# led_projek.net
KiCad netlist of a schematic drawn in EAGLE
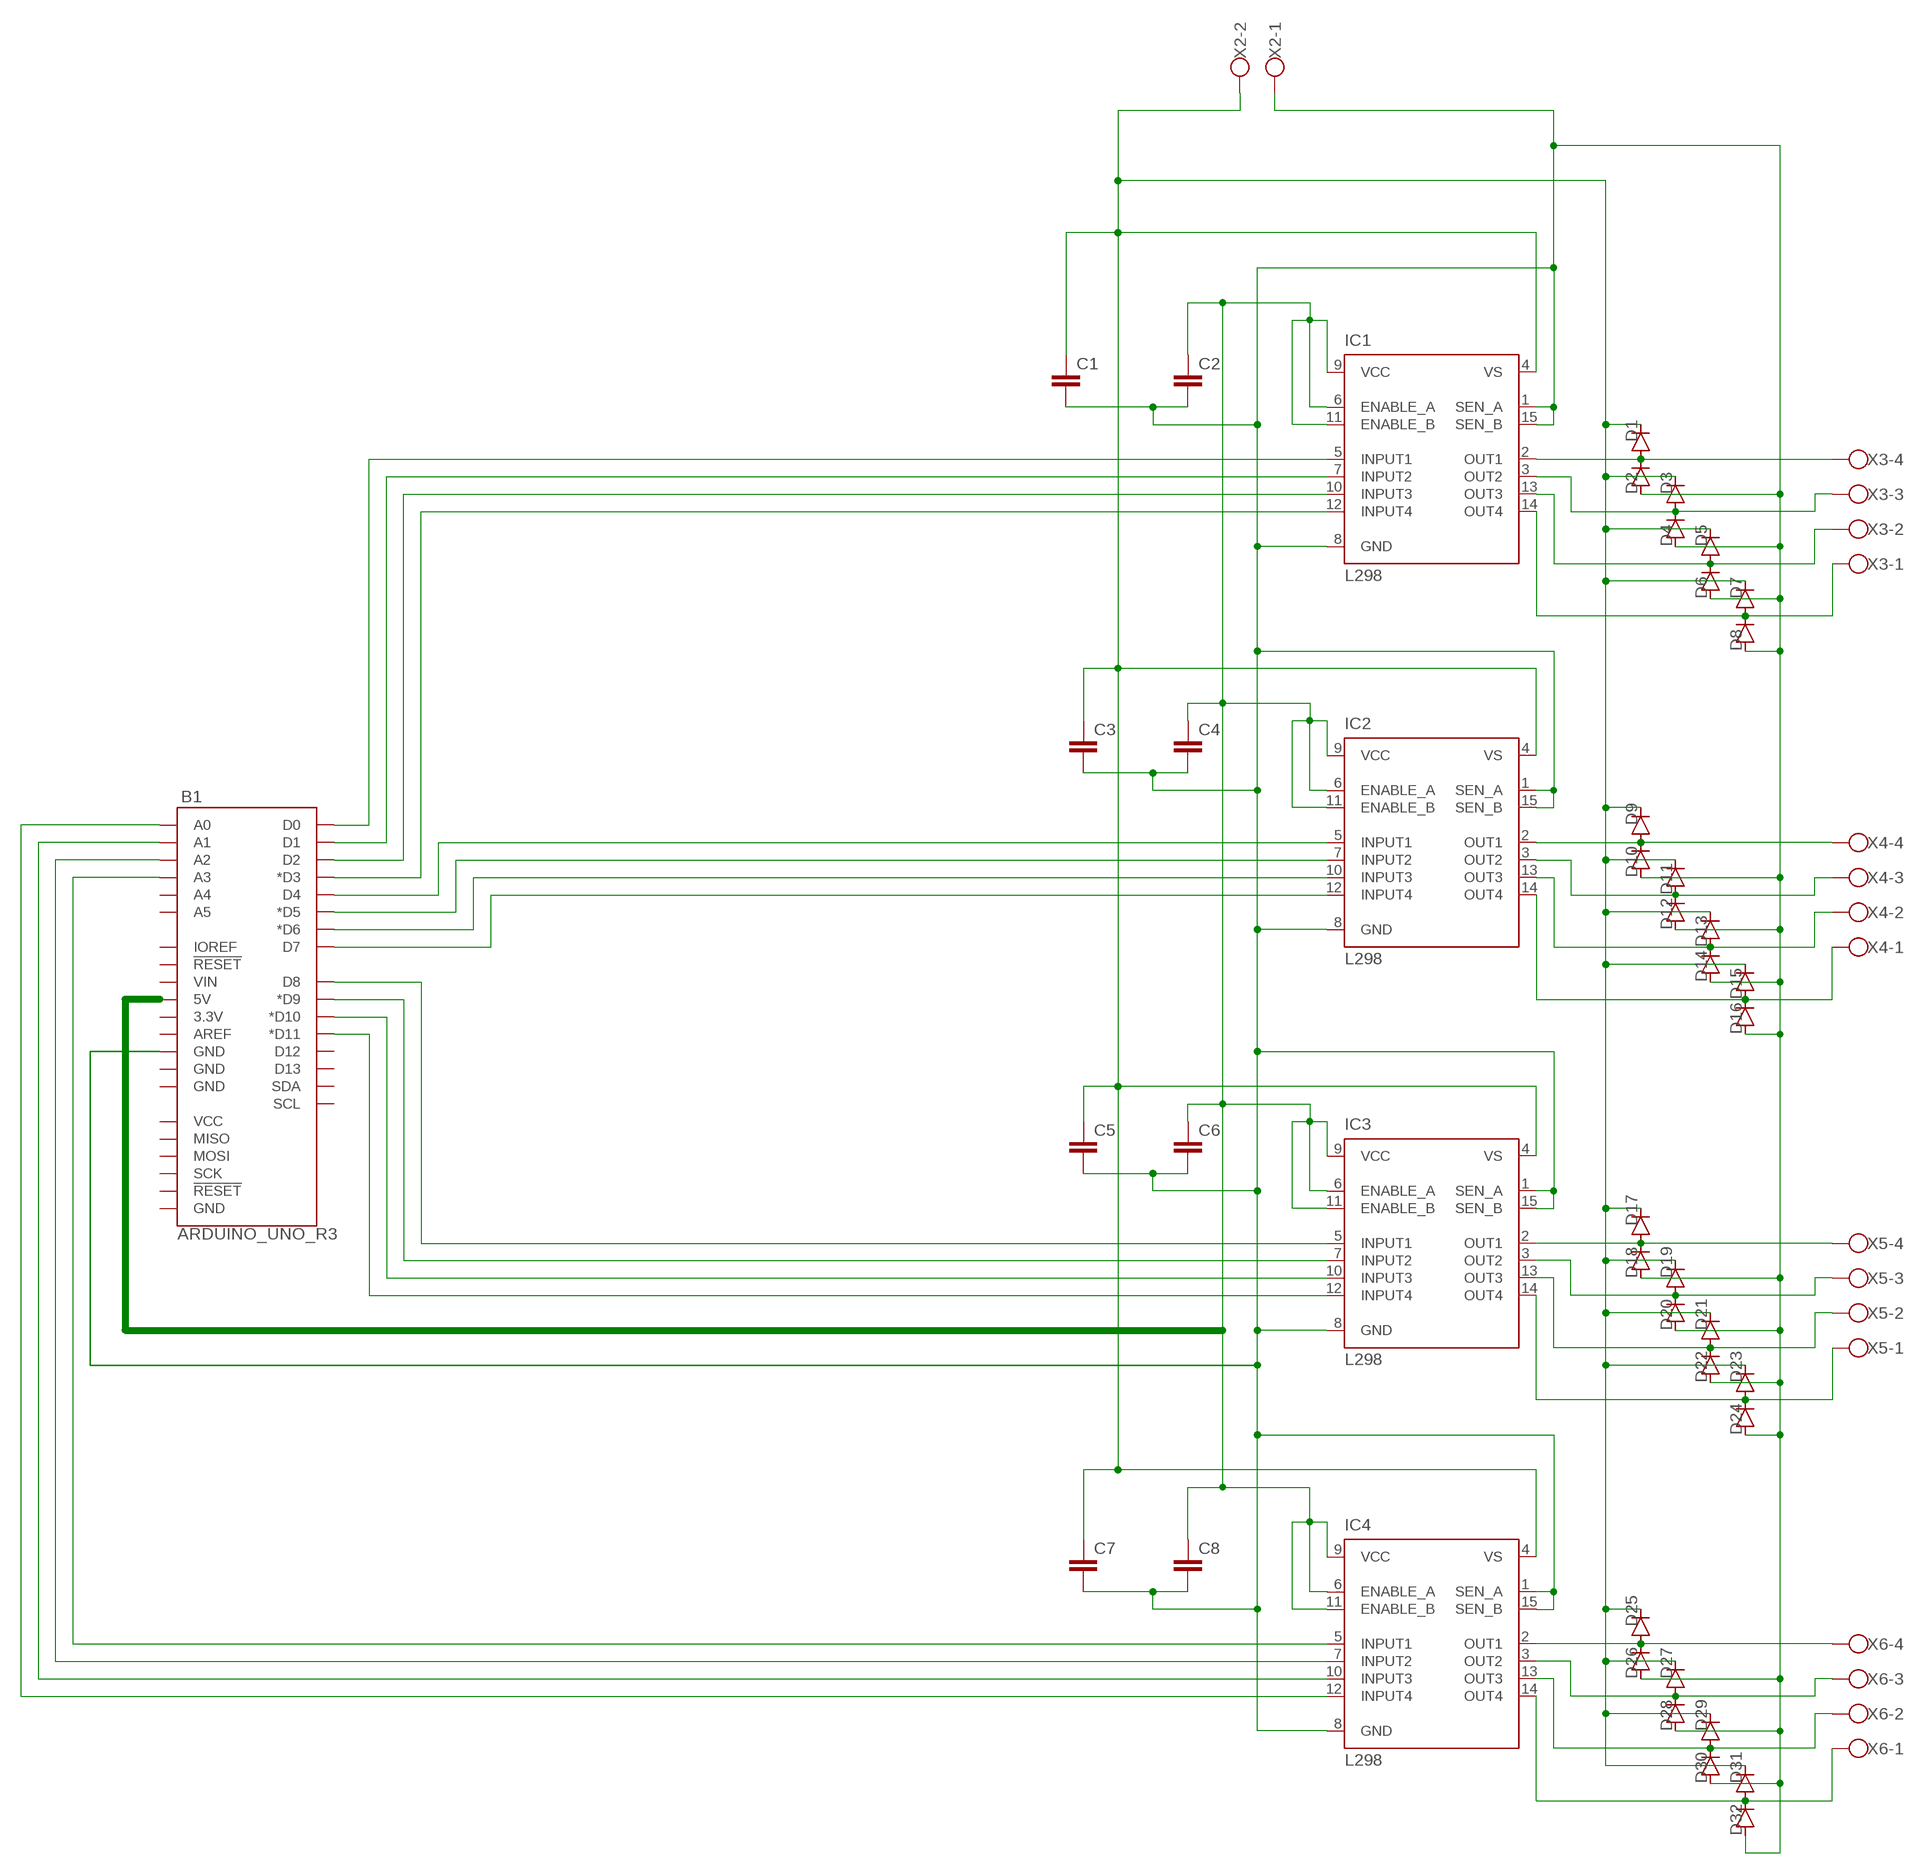
[diagram p0: schematic, sheet 1]

(export (version "E")
  (design (tool "Eeschema 10.0.6"))
  (components
    (comp (ref "B1")
      (value "ARDUINO_UNO_R3")
      (footprint "eagle-import:ARDUINO_R3")
      (libsource (lib "eagle-import") (part "ARDUINO_UNO_R3"))
    )
    (comp (ref "C1")
      (value "C-EUC0805K")
      (footprint "eagle-import:C0805K")
      (libsource (lib "eagle-import") (part "C-EUC0805K"))
    )
    (comp (ref "C2")
      (value "C-EUC0805K")
      (footprint "eagle-import:C0805K")
      (libsource (lib "eagle-import") (part "C-EUC0805K"))
    )
    (comp (ref "C3")
      (value "C-EUC0805K")
      (footprint "eagle-import:C0805K")
      (libsource (lib "eagle-import") (part "C-EUC0805K"))
    )
    (comp (ref "C4")
      (value "C-EUC0805K")
      (footprint "eagle-import:C0805K")
      (libsource (lib "eagle-import") (part "C-EUC0805K"))
    )
    (comp (ref "C5")
      (value "C-EUC0805K")
      (footprint "eagle-import:C0805K")
      (libsource (lib "eagle-import") (part "C-EUC0805K"))
    )
    (comp (ref "C6")
      (value "C-EUC0805K")
      (footprint "eagle-import:C0805K")
      (libsource (lib "eagle-import") (part "C-EUC0805K"))
    )
    (comp (ref "C7")
      (value "C-EUC0805K")
      (footprint "eagle-import:C0805K")
      (libsource (lib "eagle-import") (part "C-EUC0805K"))
    )
    (comp (ref "C8")
      (value "C-EUC0805K")
      (footprint "eagle-import:C0805K")
      (libsource (lib "eagle-import") (part "C-EUC0805K"))
    )
    (comp (ref "D1")
      (value "DIODE-DO-214AC")
      (footprint "eagle-import:DO-214AC")
      (libsource (lib "eagle-import") (part "DIODE-DO-214AC"))
    )
    (comp (ref "D2")
      (value "DIODE-DO-214AC")
      (footprint "eagle-import:DO-214AC")
      (libsource (lib "eagle-import") (part "DIODE-DO-214AC"))
    )
    (comp (ref "D3")
      (value "DIODE-DO-214AC")
      (footprint "eagle-import:DO-214AC")
      (libsource (lib "eagle-import") (part "DIODE-DO-214AC"))
    )
    (comp (ref "D4")
      (value "DIODE-DO-214AC")
      (footprint "eagle-import:DO-214AC")
      (libsource (lib "eagle-import") (part "DIODE-DO-214AC"))
    )
    (comp (ref "D5")
      (value "DIODE-DO-214AC")
      (footprint "eagle-import:DO-214AC")
      (libsource (lib "eagle-import") (part "DIODE-DO-214AC"))
    )
    (comp (ref "D6")
      (value "DIODE-DO-214AC")
      (footprint "eagle-import:DO-214AC")
      (libsource (lib "eagle-import") (part "DIODE-DO-214AC"))
    )
    (comp (ref "D7")
      (value "DIODE-DO-214AC")
      (footprint "eagle-import:DO-214AC")
      (libsource (lib "eagle-import") (part "DIODE-DO-214AC"))
    )
    (comp (ref "D8")
      (value "DIODE-DO-214AC")
      (footprint "eagle-import:DO-214AC")
      (libsource (lib "eagle-import") (part "DIODE-DO-214AC"))
    )
    (comp (ref "D9")
      (value "DIODE-DO-214AC")
      (footprint "eagle-import:DO-214AC")
      (libsource (lib "eagle-import") (part "DIODE-DO-214AC"))
    )
    (comp (ref "D10")
      (value "DIODE-DO-214AC")
      (footprint "eagle-import:DO-214AC")
      (libsource (lib "eagle-import") (part "DIODE-DO-214AC"))
    )
    (comp (ref "D11")
      (value "DIODE-DO-214AC")
      (footprint "eagle-import:DO-214AC")
      (libsource (lib "eagle-import") (part "DIODE-DO-214AC"))
    )
    (comp (ref "D12")
      (value "DIODE-DO-214AC")
      (footprint "eagle-import:DO-214AC")
      (libsource (lib "eagle-import") (part "DIODE-DO-214AC"))
    )
    (comp (ref "D13")
      (value "DIODE-DO-214AC")
      (footprint "eagle-import:DO-214AC")
      (libsource (lib "eagle-import") (part "DIODE-DO-214AC"))
    )
    (comp (ref "D14")
      (value "DIODE-DO-214AC")
      (footprint "eagle-import:DO-214AC")
      (libsource (lib "eagle-import") (part "DIODE-DO-214AC"))
    )
    (comp (ref "D15")
      (value "DIODE-DO-214AC")
      (footprint "eagle-import:DO-214AC")
      (libsource (lib "eagle-import") (part "DIODE-DO-214AC"))
    )
    (comp (ref "D16")
      (value "DIODE-DO-214AC")
      (footprint "eagle-import:DO-214AC")
      (libsource (lib "eagle-import") (part "DIODE-DO-214AC"))
    )
    (comp (ref "D17")
      (value "DIODE-DO-214AC")
      (footprint "eagle-import:DO-214AC")
      (libsource (lib "eagle-import") (part "DIODE-DO-214AC"))
    )
    (comp (ref "D18")
      (value "DIODE-DO-214AC")
      (footprint "eagle-import:DO-214AC")
      (libsource (lib "eagle-import") (part "DIODE-DO-214AC"))
    )
    (comp (ref "D19")
      (value "DIODE-DO-214AC")
      (footprint "eagle-import:DO-214AC")
      (libsource (lib "eagle-import") (part "DIODE-DO-214AC"))
    )
    (comp (ref "D20")
      (value "DIODE-DO-214AC")
      (footprint "eagle-import:DO-214AC")
      (libsource (lib "eagle-import") (part "DIODE-DO-214AC"))
    )
    (comp (ref "D21")
      (value "DIODE-DO-214AC")
      (footprint "eagle-import:DO-214AC")
      (libsource (lib "eagle-import") (part "DIODE-DO-214AC"))
    )
    (comp (ref "D22")
      (value "DIODE-DO-214AC")
      (footprint "eagle-import:DO-214AC")
      (libsource (lib "eagle-import") (part "DIODE-DO-214AC"))
    )
    (comp (ref "D23")
      (value "DIODE-DO-214AC")
      (footprint "eagle-import:DO-214AC")
      (libsource (lib "eagle-import") (part "DIODE-DO-214AC"))
    )
    (comp (ref "D24")
      (value "DIODE-DO-214AC")
      (footprint "eagle-import:DO-214AC")
      (libsource (lib "eagle-import") (part "DIODE-DO-214AC"))
    )
    (comp (ref "D25")
      (value "DIODE-DO-214AC")
      (footprint "eagle-import:DO-214AC")
      (libsource (lib "eagle-import") (part "DIODE-DO-214AC"))
    )
    (comp (ref "D26")
      (value "DIODE-DO-214AC")
      (footprint "eagle-import:DO-214AC")
      (libsource (lib "eagle-import") (part "DIODE-DO-214AC"))
    )
    (comp (ref "D27")
      (value "DIODE-DO-214AC")
      (footprint "eagle-import:DO-214AC")
      (libsource (lib "eagle-import") (part "DIODE-DO-214AC"))
    )
    (comp (ref "D28")
      (value "DIODE-DO-214AC")
      (footprint "eagle-import:DO-214AC")
      (libsource (lib "eagle-import") (part "DIODE-DO-214AC"))
    )
    (comp (ref "D29")
      (value "DIODE-DO-214AC")
      (footprint "eagle-import:DO-214AC")
      (libsource (lib "eagle-import") (part "DIODE-DO-214AC"))
    )
    (comp (ref "D30")
      (value "DIODE-DO-214AC")
      (footprint "eagle-import:DO-214AC")
      (libsource (lib "eagle-import") (part "DIODE-DO-214AC"))
    )
    (comp (ref "D31")
      (value "DIODE-DO-214AC")
      (footprint "eagle-import:DO-214AC")
      (libsource (lib "eagle-import") (part "DIODE-DO-214AC"))
    )
    (comp (ref "D32")
      (value "DIODE-DO-214AC")
      (footprint "eagle-import:DO-214AC")
      (libsource (lib "eagle-import") (part "DIODE-DO-214AC"))
    )
    (comp (ref "IC1")
      (value "L298")
      (footprint "eagle-import:MULTIWATT-15")
      (fields (field (name "MPN") "L298N"))
      (libsource (lib "eagle-import") (part "L298"))
    )
    (comp (ref "IC2")
      (value "L298")
      (footprint "eagle-import:MULTIWATT-15")
      (fields (field (name "MPN") "L298N"))
      (libsource (lib "eagle-import") (part "L298"))
    )
    (comp (ref "IC3")
      (value "L298")
      (footprint "eagle-import:MULTIWATT-15")
      (fields (field (name "MPN") "L298N"))
      (libsource (lib "eagle-import") (part "L298"))
    )
    (comp (ref "IC4")
      (value "L298")
      (footprint "eagle-import:MULTIWATT-15")
      (fields (field (name "MPN") "L298N"))
      (libsource (lib "eagle-import") (part "L298"))
    )
    (comp (ref "X2")
      (value "W237-102")
      (footprint "eagle-import:W237-102")
      (fields (field (name "MPN") "237-102"))
      (libsource (lib "eagle-import") (part "W237-102"))
    )
    (comp (ref "X3")
      (value "W237-4")
      (footprint "eagle-import:W237-4")
      (libsource (lib "eagle-import") (part "W237-4"))
    )
    (comp (ref "X4")
      (value "W237-4")
      (footprint "eagle-import:W237-4")
      (libsource (lib "eagle-import") (part "W237-4"))
    )
    (comp (ref "X5")
      (value "W237-4")
      (footprint "eagle-import:W237-4")
      (libsource (lib "eagle-import") (part "W237-4"))
    )
    (comp (ref "X6")
      (value "W237-4")
      (footprint "eagle-import:W237-4")
      (libsource (lib "eagle-import") (part "W237-4"))
    )
  )
  (nets
    (net (code "1") (name "Net-(B1-*D3)") (class "Default")
      (node (ref "B1") (pin "D3") (pinfunction "*D3_D3") (pintype "bidirectional"))
      (node (ref "IC1") (pin "12") (pinfunction "INPUT4_12") (pintype "input"))
    )
    (net (code "2") (name "Net-(B1-*D5)") (class "Default")
      (node (ref "B1") (pin "D5") (pinfunction "*D5_D5") (pintype "bidirectional"))
      (node (ref "IC2") (pin "7") (pinfunction "INPUT2_7") (pintype "input"))
    )
    (net (code "3") (name "Net-(B1-*D6)") (class "Default")
      (node (ref "B1") (pin "D6") (pinfunction "*D6_D6") (pintype "bidirectional"))
      (node (ref "IC2") (pin "10") (pinfunction "INPUT3_10") (pintype "input"))
    )
    (net (code "4") (name "Net-(B1-*D9)") (class "Default")
      (node (ref "B1") (pin "D9") (pinfunction "*D9_D9") (pintype "bidirectional"))
      (node (ref "IC3") (pin "7") (pinfunction "INPUT2_7") (pintype "input"))
    )
    (net (code "5") (name "Net-(B1-*D10)") (class "Default")
      (node (ref "B1") (pin "D10") (pinfunction "*D10_D10") (pintype "bidirectional"))
      (node (ref "IC3") (pin "10") (pinfunction "INPUT3_10") (pintype "input"))
    )
    (net (code "6") (name "Net-(B1-*D11)") (class "Default")
      (node (ref "B1") (pin "D11") (pinfunction "*D11_D11") (pintype "bidirectional"))
      (node (ref "IC3") (pin "12") (pinfunction "INPUT4_12") (pintype "input"))
    )
    (net (code "7") (name "Net-(IC1-ENABLE_A)") (class "Default")
      (node (ref "B1") (pin "5V") (pinfunction "5V_5V") (pintype "bidirectional"))
      (node (ref "C2") (pin "1") (pinfunction "1_1") (pintype "passive"))
      (node (ref "C4") (pin "1") (pinfunction "1_1") (pintype "passive"))
      (node (ref "C6") (pin "1") (pinfunction "1_1") (pintype "passive"))
      (node (ref "C8") (pin "1") (pinfunction "1_1") (pintype "passive"))
      (node (ref "IC1") (pin "11") (pinfunction "ENABLE_B_11") (pintype "input"))
      (node (ref "IC1") (pin "6") (pinfunction "ENABLE_A_6") (pintype "input"))
      (node (ref "IC1") (pin "9") (pinfunction "VCC_9") (pintype "power_in"))
      (node (ref "IC2") (pin "11") (pinfunction "ENABLE_B_11") (pintype "input"))
      (node (ref "IC2") (pin "6") (pinfunction "ENABLE_A_6") (pintype "input"))
      (node (ref "IC2") (pin "9") (pinfunction "VCC_9") (pintype "power_in"))
      (node (ref "IC3") (pin "11") (pinfunction "ENABLE_B_11") (pintype "input"))
      (node (ref "IC3") (pin "6") (pinfunction "ENABLE_A_6") (pintype "input"))
      (node (ref "IC3") (pin "9") (pinfunction "VCC_9") (pintype "power_in"))
      (node (ref "IC4") (pin "11") (pinfunction "ENABLE_B_11") (pintype "input"))
      (node (ref "IC4") (pin "6") (pinfunction "ENABLE_A_6") (pintype "input"))
      (node (ref "IC4") (pin "9") (pinfunction "VCC_9") (pintype "power_in"))
    )
    (net (code "8") (name "Net-(IC1-GND)") (class "Default")
      (node (ref "B1") (pin "GND@4") (pinfunction "GND_GND@4") (pintype "bidirectional"))
      (node (ref "C1") (pin "2") (pinfunction "2_2") (pintype "passive"))
      (node (ref "C2") (pin "2") (pinfunction "2_2") (pintype "passive"))
      (node (ref "C3") (pin "2") (pinfunction "2_2") (pintype "passive"))
      (node (ref "C4") (pin "2") (pinfunction "2_2") (pintype "passive"))
      (node (ref "C5") (pin "2") (pinfunction "2_2") (pintype "passive"))
      (node (ref "C6") (pin "2") (pinfunction "2_2") (pintype "passive"))
      (node (ref "C7") (pin "2") (pinfunction "2_2") (pintype "passive"))
      (node (ref "C8") (pin "2") (pinfunction "2_2") (pintype "passive"))
      (node (ref "D10") (pin "A") (pinfunction "A_A") (pintype "passive"))
      (node (ref "D12") (pin "A") (pinfunction "A_A") (pintype "passive"))
      (node (ref "D14") (pin "A") (pinfunction "A_A") (pintype "passive"))
      (node (ref "D16") (pin "A") (pinfunction "A_A") (pintype "passive"))
      (node (ref "D18") (pin "A") (pinfunction "A_A") (pintype "passive"))
      (node (ref "D2") (pin "A") (pinfunction "A_A") (pintype "passive"))
      (node (ref "D20") (pin "A") (pinfunction "A_A") (pintype "passive"))
      (node (ref "D22") (pin "A") (pinfunction "A_A") (pintype "passive"))
      (node (ref "D24") (pin "A") (pinfunction "A_A") (pintype "passive"))
      (node (ref "D26") (pin "A") (pinfunction "A_A") (pintype "passive"))
      (node (ref "D28") (pin "A") (pinfunction "A_A") (pintype "passive"))
      (node (ref "D30") (pin "A") (pinfunction "A_A") (pintype "passive"))
      (node (ref "D32") (pin "A") (pinfunction "A_A") (pintype "passive"))
      (node (ref "D4") (pin "A") (pinfunction "A_A") (pintype "passive"))
      (node (ref "D6") (pin "A") (pinfunction "A_A") (pintype "passive"))
      (node (ref "D8") (pin "A") (pinfunction "A_A") (pintype "passive"))
      (node (ref "IC1") (pin "1") (pinfunction "SEN_A_1") (pintype "input"))
      (node (ref "IC1") (pin "15") (pinfunction "SEN_B_15") (pintype "input"))
      (node (ref "IC1") (pin "8") (pinfunction "GND_8") (pintype "power_in"))
      (node (ref "IC2") (pin "1") (pinfunction "SEN_A_1") (pintype "input"))
      (node (ref "IC2") (pin "15") (pinfunction "SEN_B_15") (pintype "input"))
      (node (ref "IC2") (pin "8") (pinfunction "GND_8") (pintype "power_in"))
      (node (ref "IC3") (pin "1") (pinfunction "SEN_A_1") (pintype "input"))
      (node (ref "IC3") (pin "15") (pinfunction "SEN_B_15") (pintype "input"))
      (node (ref "IC3") (pin "8") (pinfunction "GND_8") (pintype "power_in"))
      (node (ref "IC4") (pin "1") (pinfunction "SEN_A_1") (pintype "input"))
      (node (ref "IC4") (pin "15") (pinfunction "SEN_B_15") (pintype "input"))
      (node (ref "IC4") (pin "8") (pinfunction "GND_8") (pintype "power_in"))
      (node (ref "X2") (pin "1") (pinfunction "KL_1") (pintype "passive"))
    )
    (net (code "9") (name "Net-(IC1-INPUT1)") (class "Default")
      (node (ref "B1") (pin "D0") (pinfunction "D0_D0") (pintype "bidirectional"))
      (node (ref "IC1") (pin "5") (pinfunction "INPUT1_5") (pintype "input"))
    )
    (net (code "10") (name "Net-(IC1-INPUT2)") (class "Default")
      (node (ref "B1") (pin "D1") (pinfunction "D1_D1") (pintype "bidirectional"))
      (node (ref "IC1") (pin "7") (pinfunction "INPUT2_7") (pintype "input"))
    )
    (net (code "11") (name "Net-(IC1-INPUT3)") (class "Default")
      (node (ref "B1") (pin "D2") (pinfunction "D2_D2") (pintype "bidirectional"))
      (node (ref "IC1") (pin "10") (pinfunction "INPUT3_10") (pintype "input"))
    )
    (net (code "12") (name "Net-(IC1-OUT1)") (class "Default")
      (node (ref "D1") (pin "A") (pinfunction "A_A") (pintype "passive"))
      (node (ref "D2") (pin "C") (pinfunction "C_C") (pintype "passive"))
      (node (ref "IC1") (pin "2") (pinfunction "OUT1_2") (pintype "output"))
      (node (ref "X3") (pin "4") (pinfunction "KL_4") (pintype "passive"))
    )
    (net (code "13") (name "Net-(IC1-OUT2)") (class "Default")
      (node (ref "D3") (pin "A") (pinfunction "A_A") (pintype "passive"))
      (node (ref "D4") (pin "C") (pinfunction "C_C") (pintype "passive"))
      (node (ref "IC1") (pin "3") (pinfunction "OUT2_3") (pintype "output"))
      (node (ref "X3") (pin "3") (pinfunction "KL_3") (pintype "passive"))
    )
    (net (code "14") (name "Net-(IC1-OUT3)") (class "Default")
      (node (ref "D5") (pin "A") (pinfunction "A_A") (pintype "passive"))
      (node (ref "D6") (pin "C") (pinfunction "C_C") (pintype "passive"))
      (node (ref "IC1") (pin "13") (pinfunction "OUT3_13") (pintype "output"))
      (node (ref "X3") (pin "2") (pinfunction "KL_2") (pintype "passive"))
    )
    (net (code "15") (name "Net-(IC1-OUT4)") (class "Default")
      (node (ref "D7") (pin "A") (pinfunction "A_A") (pintype "passive"))
      (node (ref "D8") (pin "C") (pinfunction "C_C") (pintype "passive"))
      (node (ref "IC1") (pin "14") (pinfunction "OUT4_14") (pintype "output"))
      (node (ref "X3") (pin "1") (pinfunction "KL_1") (pintype "passive"))
    )
    (net (code "16") (name "Net-(IC1-VS)") (class "Default")
      (node (ref "C1") (pin "1") (pinfunction "1_1") (pintype "passive"))
      (node (ref "C3") (pin "1") (pinfunction "1_1") (pintype "passive"))
      (node (ref "C5") (pin "1") (pinfunction "1_1") (pintype "passive"))
      (node (ref "C7") (pin "1") (pinfunction "1_1") (pintype "passive"))
      (node (ref "D1") (pin "C") (pinfunction "C_C") (pintype "passive"))
      (node (ref "D11") (pin "C") (pinfunction "C_C") (pintype "passive"))
      (node (ref "D13") (pin "C") (pinfunction "C_C") (pintype "passive"))
      (node (ref "D15") (pin "C") (pinfunction "C_C") (pintype "passive"))
      (node (ref "D17") (pin "C") (pinfunction "C_C") (pintype "passive"))
      (node (ref "D19") (pin "C") (pinfunction "C_C") (pintype "passive"))
      (node (ref "D21") (pin "C") (pinfunction "C_C") (pintype "passive"))
      (node (ref "D23") (pin "C") (pinfunction "C_C") (pintype "passive"))
      (node (ref "D25") (pin "C") (pinfunction "C_C") (pintype "passive"))
      (node (ref "D27") (pin "C") (pinfunction "C_C") (pintype "passive"))
      (node (ref "D29") (pin "C") (pinfunction "C_C") (pintype "passive"))
      (node (ref "D3") (pin "C") (pinfunction "C_C") (pintype "passive"))
      (node (ref "D31") (pin "C") (pinfunction "C_C") (pintype "passive"))
      (node (ref "D5") (pin "C") (pinfunction "C_C") (pintype "passive"))
      (node (ref "D7") (pin "C") (pinfunction "C_C") (pintype "passive"))
      (node (ref "D9") (pin "C") (pinfunction "C_C") (pintype "passive"))
      (node (ref "IC1") (pin "4") (pinfunction "VS_4") (pintype "power_in"))
      (node (ref "IC2") (pin "4") (pinfunction "VS_4") (pintype "power_in"))
      (node (ref "IC3") (pin "4") (pinfunction "VS_4") (pintype "power_in"))
      (node (ref "IC4") (pin "4") (pinfunction "VS_4") (pintype "power_in"))
      (node (ref "X2") (pin "2") (pinfunction "KL_2") (pintype "passive"))
    )
    (net (code "17") (name "Net-(IC2-INPUT1)") (class "Default")
      (node (ref "B1") (pin "D4") (pinfunction "D4_D4") (pintype "bidirectional"))
      (node (ref "IC2") (pin "5") (pinfunction "INPUT1_5") (pintype "input"))
    )
    (net (code "18") (name "Net-(IC2-INPUT4)") (class "Default")
      (node (ref "B1") (pin "D7") (pinfunction "D7_D7") (pintype "bidirectional"))
      (node (ref "IC2") (pin "12") (pinfunction "INPUT4_12") (pintype "input"))
    )
    (net (code "19") (name "Net-(IC2-OUT1)") (class "Default")
      (node (ref "D10") (pin "C") (pinfunction "C_C") (pintype "passive"))
      (node (ref "D9") (pin "A") (pinfunction "A_A") (pintype "passive"))
      (node (ref "IC2") (pin "2") (pinfunction "OUT1_2") (pintype "output"))
      (node (ref "X4") (pin "4") (pinfunction "KL_4") (pintype "passive"))
    )
    (net (code "20") (name "Net-(IC2-OUT2)") (class "Default")
      (node (ref "D11") (pin "A") (pinfunction "A_A") (pintype "passive"))
      (node (ref "D12") (pin "C") (pinfunction "C_C") (pintype "passive"))
      (node (ref "IC2") (pin "3") (pinfunction "OUT2_3") (pintype "output"))
      (node (ref "X4") (pin "3") (pinfunction "KL_3") (pintype "passive"))
    )
    (net (code "21") (name "Net-(IC2-OUT3)") (class "Default")
      (node (ref "D13") (pin "A") (pinfunction "A_A") (pintype "passive"))
      (node (ref "D14") (pin "C") (pinfunction "C_C") (pintype "passive"))
      (node (ref "IC2") (pin "13") (pinfunction "OUT3_13") (pintype "output"))
      (node (ref "X4") (pin "2") (pinfunction "KL_2") (pintype "passive"))
    )
    (net (code "22") (name "Net-(IC2-OUT4)") (class "Default")
      (node (ref "D15") (pin "A") (pinfunction "A_A") (pintype "passive"))
      (node (ref "D16") (pin "C") (pinfunction "C_C") (pintype "passive"))
      (node (ref "IC2") (pin "14") (pinfunction "OUT4_14") (pintype "output"))
      (node (ref "X4") (pin "1") (pinfunction "KL_1") (pintype "passive"))
    )
    (net (code "23") (name "Net-(IC3-INPUT1)") (class "Default")
      (node (ref "B1") (pin "D8") (pinfunction "D8_D8") (pintype "bidirectional"))
      (node (ref "IC3") (pin "5") (pinfunction "INPUT1_5") (pintype "input"))
    )
    (net (code "24") (name "Net-(IC3-OUT1)") (class "Default")
      (node (ref "D17") (pin "A") (pinfunction "A_A") (pintype "passive"))
      (node (ref "D18") (pin "C") (pinfunction "C_C") (pintype "passive"))
      (node (ref "IC3") (pin "2") (pinfunction "OUT1_2") (pintype "output"))
      (node (ref "X5") (pin "4") (pinfunction "KL_4") (pintype "passive"))
    )
    (net (code "25") (name "Net-(IC3-OUT2)") (class "Default")
      (node (ref "D19") (pin "A") (pinfunction "A_A") (pintype "passive"))
      (node (ref "D20") (pin "C") (pinfunction "C_C") (pintype "passive"))
      (node (ref "IC3") (pin "3") (pinfunction "OUT2_3") (pintype "output"))
      (node (ref "X5") (pin "3") (pinfunction "KL_3") (pintype "passive"))
    )
    (net (code "26") (name "Net-(IC3-OUT3)") (class "Default")
      (node (ref "D21") (pin "A") (pinfunction "A_A") (pintype "passive"))
      (node (ref "D22") (pin "C") (pinfunction "C_C") (pintype "passive"))
      (node (ref "IC3") (pin "13") (pinfunction "OUT3_13") (pintype "output"))
      (node (ref "X5") (pin "2") (pinfunction "KL_2") (pintype "passive"))
    )
    (net (code "27") (name "Net-(IC3-OUT4)") (class "Default")
      (node (ref "D23") (pin "A") (pinfunction "A_A") (pintype "passive"))
      (node (ref "D24") (pin "C") (pinfunction "C_C") (pintype "passive"))
      (node (ref "IC3") (pin "14") (pinfunction "OUT4_14") (pintype "output"))
      (node (ref "X5") (pin "1") (pinfunction "KL_1") (pintype "passive"))
    )
    (net (code "28") (name "Net-(IC4-INPUT1)") (class "Default")
      (node (ref "B1") (pin "A3") (pinfunction "A3_A3") (pintype "bidirectional"))
      (node (ref "IC4") (pin "5") (pinfunction "INPUT1_5") (pintype "input"))
    )
    (net (code "29") (name "Net-(IC4-INPUT2)") (class "Default")
      (node (ref "B1") (pin "A2") (pinfunction "A2_A2") (pintype "bidirectional"))
      (node (ref "IC4") (pin "7") (pinfunction "INPUT2_7") (pintype "input"))
    )
    (net (code "30") (name "Net-(IC4-INPUT3)") (class "Default")
      (node (ref "B1") (pin "A1") (pinfunction "A1_A1") (pintype "bidirectional"))
      (node (ref "IC4") (pin "10") (pinfunction "INPUT3_10") (pintype "input"))
    )
    (net (code "31") (name "Net-(IC4-INPUT4)") (class "Default")
      (node (ref "B1") (pin "A0") (pinfunction "A0_A0") (pintype "bidirectional"))
      (node (ref "IC4") (pin "12") (pinfunction "INPUT4_12") (pintype "input"))
    )
    (net (code "32") (name "Net-(IC4-OUT1)") (class "Default")
      (node (ref "D25") (pin "A") (pinfunction "A_A") (pintype "passive"))
      (node (ref "D26") (pin "C") (pinfunction "C_C") (pintype "passive"))
      (node (ref "IC4") (pin "2") (pinfunction "OUT1_2") (pintype "output"))
      (node (ref "X6") (pin "4") (pinfunction "KL_4") (pintype "passive"))
    )
    (net (code "33") (name "Net-(IC4-OUT2)") (class "Default")
      (node (ref "D27") (pin "A") (pinfunction "A_A") (pintype "passive"))
      (node (ref "D28") (pin "C") (pinfunction "C_C") (pintype "passive"))
      (node (ref "IC4") (pin "3") (pinfunction "OUT2_3") (pintype "output"))
      (node (ref "X6") (pin "3") (pinfunction "KL_3") (pintype "passive"))
    )
    (net (code "34") (name "Net-(IC4-OUT3)") (class "Default")
      (node (ref "D29") (pin "A") (pinfunction "A_A") (pintype "passive"))
      (node (ref "D30") (pin "C") (pinfunction "C_C") (pintype "passive"))
      (node (ref "IC4") (pin "13") (pinfunction "OUT3_13") (pintype "output"))
      (node (ref "X6") (pin "2") (pinfunction "KL_2") (pintype "passive"))
    )
    (net (code "35") (name "Net-(IC4-OUT4)") (class "Default")
      (node (ref "D31") (pin "A") (pinfunction "A_A") (pintype "passive"))
      (node (ref "D32") (pin "C") (pinfunction "C_C") (pintype "passive"))
      (node (ref "IC4") (pin "14") (pinfunction "OUT4_14") (pintype "output"))
      (node (ref "X6") (pin "1") (pinfunction "KL_1") (pintype "passive"))
    )
    (net (code "36") (name "unconnected-(B1-GND-PadGND@1)") (class "Default")
      (node (ref "B1") (pin "GND@1") (pinfunction "GND_GND@1") (pintype "bidirectional"))
    )
    (net (code "37") (name "unconnected-(B1-GND-PadGND@2)") (class "Default")
      (node (ref "B1") (pin "GND@2") (pinfunction "GND_GND@2") (pintype "bidirectional"))
    )
    (net (code "38") (name "unconnected-(B1-GND-PadGND@3)") (class "Default")
      (node (ref "B1") (pin "GND@3") (pinfunction "GND_GND@3") (pintype "bidirectional"))
    )
    (net (code "39") (name "unconnected-(B1-Pad3.3V)") (class "Default")
      (node (ref "B1") (pin "3.3V") (pinfunction "3.3V_3.3V") (pintype "bidirectional"))
    )
    (net (code "40") (name "unconnected-(B1-PadA4)") (class "Default")
      (node (ref "B1") (pin "A4") (pinfunction "A4_A4") (pintype "bidirectional"))
    )
    (net (code "41") (name "unconnected-(B1-PadA5)") (class "Default")
      (node (ref "B1") (pin "A5") (pinfunction "A5_A5") (pintype "bidirectional"))
    )
    (net (code "42") (name "unconnected-(B1-PadAREF)") (class "Default")
      (node (ref "B1") (pin "AREF") (pinfunction "AREF_AREF") (pintype "bidirectional"))
    )
    (net (code "43") (name "unconnected-(B1-PadD12)") (class "Default")
      (node (ref "B1") (pin "D12") (pinfunction "D12_D12") (pintype "bidirectional"))
    )
    (net (code "44") (name "unconnected-(B1-PadD13)") (class "Default")
      (node (ref "B1") (pin "D13") (pinfunction "D13_D13") (pintype "bidirectional"))
    )
    (net (code "45") (name "unconnected-(B1-PadIOREF)") (class "Default")
      (node (ref "B1") (pin "IOREF") (pinfunction "IOREF_IOREF") (pintype "bidirectional"))
    )
    (net (code "46") (name "unconnected-(B1-PadMISO)") (class "Default")
      (node (ref "B1") (pin "MISO") (pinfunction "MISO_MISO") (pintype "bidirectional"))
    )
    (net (code "47") (name "unconnected-(B1-PadMOSI)") (class "Default")
      (node (ref "B1") (pin "MOSI") (pinfunction "MOSI_MOSI") (pintype "bidirectional"))
    )
    (net (code "48") (name "unconnected-(B1-PadSCK)") (class "Default")
      (node (ref "B1") (pin "SCK") (pinfunction "SCK_SCK") (pintype "bidirectional"))
    )
    (net (code "49") (name "unconnected-(B1-PadSCL)") (class "Default")
      (node (ref "B1") (pin "SCL") (pinfunction "SCL_SCL") (pintype "bidirectional"))
    )
    (net (code "50") (name "unconnected-(B1-PadSDA)") (class "Default")
      (node (ref "B1") (pin "SDA") (pinfunction "SDA_SDA") (pintype "bidirectional"))
    )
    (net (code "51") (name "unconnected-(B1-PadVCC)") (class "Default")
      (node (ref "B1") (pin "VCC") (pinfunction "VCC_VCC") (pintype "bidirectional"))
    )
    (net (code "52") (name "unconnected-(B1-PadVIN)") (class "Default")
      (node (ref "B1") (pin "VIN") (pinfunction "VIN_VIN") (pintype "bidirectional"))
    )
    (net (code "53") (name "unconnected-(B1-~{RESET}-PadRESET@1)") (class "Default")
      (node (ref "B1") (pin "RESET@1") (pinfunction "~{RESET}_RESET@1") (pintype "bidirectional"))
    )
    (net (code "54") (name "unconnected-(B1-~{RESET}-PadRESET@2)") (class "Default")
      (node (ref "B1") (pin "RESET@2") (pinfunction "~{RESET}_RESET@2") (pintype "bidirectional"))
    )
  )
)
